# SDRAMModule.net
KiCad netlist of a schematic drawn in Altium Designer
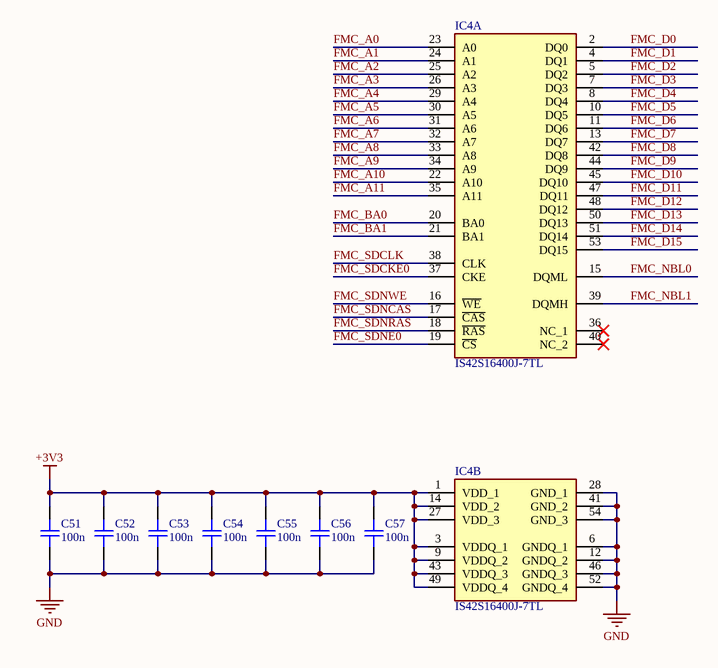
[diagram p0: SDRAMModule.SchDoc]

(export (version "E")
  (design (tool "Eeschema 10.0.6"))
  (components
    (comp (ref "C51")
      (value "100n")
      (footprint "CAP_0402")
      (description "Capacitor SMD 0402")
      (libsource (lib "Schematic-Lib-PhilsLab") (part "CAP_0402"))
    )
    (comp (ref "C52")
      (value "100n")
      (footprint "CAP_0402")
      (description "Capacitor SMD 0402")
      (libsource (lib "Schematic-Lib-PhilsLab") (part "CAP_0402"))
    )
    (comp (ref "C53")
      (value "100n")
      (footprint "CAP_0402")
      (description "Capacitor SMD 0402")
      (libsource (lib "Schematic-Lib-PhilsLab") (part "CAP_0402"))
    )
    (comp (ref "C54")
      (value "100n")
      (footprint "CAP_0402")
      (description "Capacitor SMD 0402")
      (libsource (lib "Schematic-Lib-PhilsLab") (part "CAP_0402"))
    )
    (comp (ref "C55")
      (value "100n")
      (footprint "CAP_0402")
      (description "Capacitor SMD 0402")
      (libsource (lib "Schematic-Lib-PhilsLab") (part "CAP_0402"))
    )
    (comp (ref "C56")
      (value "100n")
      (footprint "CAP_0402")
      (description "Capacitor SMD 0402")
      (libsource (lib "Schematic-Lib-PhilsLab") (part "CAP_0402"))
    )
    (comp (ref "C57")
      (value "100n")
      (footprint "CAP_0402")
      (description "Capacitor SMD 0402")
      (libsource (lib "Schematic-Lib-PhilsLab") (part "CAP_0402"))
    )
    (comp (ref "IC4")
      (value "IS42S16400J-7TL")
      (footprint "Footprint-Lib-PhilsLab:SOP80P1176X120-54N")
      (description "Integrated Circuit")
      (fields (field (name "MOUSER PART NUMBER") "870-IS42S16400J-7TL"))
      (libsource (lib "Schematic-Lib-PhilsLab") (part "IS42S16400J-7TL"))
    )
  )
  (nets
    (net (code "1") (name "+3V3") (class "Default")
      (node (ref "C51") (pin "2") (pinfunction "2_2") (pintype "passive"))
      (node (ref "C52") (pin "2") (pinfunction "2_2") (pintype "passive"))
      (node (ref "C53") (pin "2") (pinfunction "2_2") (pintype "passive"))
      (node (ref "C54") (pin "2") (pinfunction "2_2") (pintype "passive"))
      (node (ref "C55") (pin "2") (pinfunction "2_2") (pintype "passive"))
      (node (ref "C56") (pin "2") (pinfunction "2_2") (pintype "passive"))
      (node (ref "C57") (pin "2") (pinfunction "2_2") (pintype "passive"))
      (node (ref "IC4") (pin "1") (pinfunction "VDD_1_1") (pintype "passive"))
      (node (ref "IC4") (pin "14") (pinfunction "VDD_2_14") (pintype "passive"))
      (node (ref "IC4") (pin "27") (pinfunction "VDD_3_27") (pintype "passive"))
      (node (ref "IC4") (pin "3") (pinfunction "VDDQ_1_3") (pintype "passive"))
      (node (ref "IC4") (pin "43") (pinfunction "VDDQ_3_43") (pintype "passive"))
      (node (ref "IC4") (pin "49") (pinfunction "VDDQ_4_49") (pintype "passive"))
      (node (ref "IC4") (pin "9") (pinfunction "VDDQ_2_9") (pintype "passive"))
    )
    (net (code "2") (name "/FMC_A0") (class "Default")
      (node (ref "IC4") (pin "23") (pinfunction "A0_23") (pintype "passive"))
    )
    (net (code "3") (name "/FMC_A1") (class "Default")
      (node (ref "IC4") (pin "24") (pinfunction "A1_24") (pintype "passive"))
    )
    (net (code "4") (name "/FMC_A2") (class "Default")
      (node (ref "IC4") (pin "25") (pinfunction "A2_25") (pintype "passive"))
    )
    (net (code "5") (name "/FMC_A3") (class "Default")
      (node (ref "IC4") (pin "26") (pinfunction "A3_26") (pintype "passive"))
    )
    (net (code "6") (name "/FMC_A4") (class "Default")
      (node (ref "IC4") (pin "29") (pinfunction "A4_29") (pintype "passive"))
    )
    (net (code "7") (name "/FMC_A5") (class "Default")
      (node (ref "IC4") (pin "30") (pinfunction "A5_30") (pintype "passive"))
    )
    (net (code "8") (name "/FMC_A6") (class "Default")
      (node (ref "IC4") (pin "31") (pinfunction "A6_31") (pintype "passive"))
    )
    (net (code "9") (name "/FMC_A7") (class "Default")
      (node (ref "IC4") (pin "32") (pinfunction "A7_32") (pintype "passive"))
    )
    (net (code "10") (name "/FMC_A8") (class "Default")
      (node (ref "IC4") (pin "33") (pinfunction "A8_33") (pintype "passive"))
    )
    (net (code "11") (name "/FMC_A9") (class "Default")
      (node (ref "IC4") (pin "34") (pinfunction "A9_34") (pintype "passive"))
    )
    (net (code "12") (name "/FMC_A10") (class "Default")
      (node (ref "IC4") (pin "22") (pinfunction "A10_22") (pintype "passive"))
    )
    (net (code "13") (name "/FMC_A11") (class "Default")
      (node (ref "IC4") (pin "35") (pinfunction "A11_35") (pintype "passive"))
    )
    (net (code "14") (name "/FMC_BA0") (class "Default")
      (node (ref "IC4") (pin "20") (pinfunction "BA0_20") (pintype "passive"))
    )
    (net (code "15") (name "/FMC_BA1") (class "Default")
      (node (ref "IC4") (pin "21") (pinfunction "BA1_21") (pintype "passive"))
    )
    (net (code "16") (name "/FMC_D0") (class "Default")
      (node (ref "IC4") (pin "2") (pinfunction "DQ0_2") (pintype "passive"))
    )
    (net (code "17") (name "/FMC_D1") (class "Default")
      (node (ref "IC4") (pin "4") (pinfunction "DQ1_4") (pintype "passive"))
    )
    (net (code "18") (name "/FMC_D2") (class "Default")
      (node (ref "IC4") (pin "5") (pinfunction "DQ2_5") (pintype "passive"))
    )
    (net (code "19") (name "/FMC_D3") (class "Default")
      (node (ref "IC4") (pin "7") (pinfunction "DQ3_7") (pintype "passive"))
    )
    (net (code "20") (name "/FMC_D4") (class "Default")
      (node (ref "IC4") (pin "8") (pinfunction "DQ4_8") (pintype "passive"))
    )
    (net (code "21") (name "/FMC_D5") (class "Default")
      (node (ref "IC4") (pin "10") (pinfunction "DQ5_10") (pintype "passive"))
    )
    (net (code "22") (name "/FMC_D6") (class "Default")
      (node (ref "IC4") (pin "11") (pinfunction "DQ6_11") (pintype "passive"))
    )
    (net (code "23") (name "/FMC_D7") (class "Default")
      (node (ref "IC4") (pin "13") (pinfunction "DQ7_13") (pintype "passive"))
    )
    (net (code "24") (name "/FMC_D8") (class "Default")
      (node (ref "IC4") (pin "42") (pinfunction "DQ8_42") (pintype "passive"))
    )
    (net (code "25") (name "/FMC_D9") (class "Default")
      (node (ref "IC4") (pin "44") (pinfunction "DQ9_44") (pintype "passive"))
    )
    (net (code "26") (name "/FMC_D10") (class "Default")
      (node (ref "IC4") (pin "45") (pinfunction "DQ10_45") (pintype "passive"))
    )
    (net (code "27") (name "/FMC_D11") (class "Default")
      (node (ref "IC4") (pin "47") (pinfunction "DQ11_47") (pintype "passive"))
    )
    (net (code "28") (name "/FMC_D12") (class "Default")
      (node (ref "IC4") (pin "48") (pinfunction "DQ12_48") (pintype "passive"))
    )
    (net (code "29") (name "/FMC_D13") (class "Default")
      (node (ref "IC4") (pin "50") (pinfunction "DQ13_50") (pintype "passive"))
    )
    (net (code "30") (name "/FMC_D14") (class "Default")
      (node (ref "IC4") (pin "51") (pinfunction "DQ14_51") (pintype "passive"))
    )
    (net (code "31") (name "/FMC_D15") (class "Default")
      (node (ref "IC4") (pin "53") (pinfunction "DQ15_53") (pintype "passive"))
    )
    (net (code "32") (name "/FMC_NBL0") (class "Default")
      (node (ref "IC4") (pin "15") (pinfunction "DQML_15") (pintype "passive"))
    )
    (net (code "33") (name "/FMC_NBL1") (class "Default")
      (node (ref "IC4") (pin "39") (pinfunction "DQMH_39") (pintype "passive"))
    )
    (net (code "34") (name "/FMC_SDCKE0") (class "Default")
      (node (ref "IC4") (pin "37") (pinfunction "CKE_37") (pintype "passive"))
    )
    (net (code "35") (name "/FMC_SDCLK") (class "Default")
      (node (ref "IC4") (pin "38") (pinfunction "CLK_38") (pintype "passive"))
    )
    (net (code "36") (name "/FMC_SDNCAS") (class "Default")
      (node (ref "IC4") (pin "17") (pinfunction "~{CAS}_17") (pintype "passive"))
    )
    (net (code "37") (name "/FMC_SDNE0") (class "Default")
      (node (ref "IC4") (pin "19") (pinfunction "~{CS}_19") (pintype "passive"))
    )
    (net (code "38") (name "/FMC_SDNRAS") (class "Default")
      (node (ref "IC4") (pin "18") (pinfunction "~{RAS}_18") (pintype "passive"))
    )
    (net (code "39") (name "/FMC_SDNWE") (class "Default")
      (node (ref "IC4") (pin "16") (pinfunction "~{WE}_16") (pintype "passive"))
    )
    (net (code "40") (name "GND") (class "Default")
      (node (ref "C51") (pin "1") (pinfunction "1_1") (pintype "passive"))
      (node (ref "C52") (pin "1") (pinfunction "1_1") (pintype "passive"))
      (node (ref "C53") (pin "1") (pinfunction "1_1") (pintype "passive"))
      (node (ref "C54") (pin "1") (pinfunction "1_1") (pintype "passive"))
      (node (ref "C55") (pin "1") (pinfunction "1_1") (pintype "passive"))
      (node (ref "C56") (pin "1") (pinfunction "1_1") (pintype "passive"))
      (node (ref "C57") (pin "1") (pinfunction "1_1") (pintype "passive"))
      (node (ref "IC4") (pin "12") (pinfunction "GNDQ_2_12") (pintype "passive"))
      (node (ref "IC4") (pin "28") (pinfunction "GND_1_28") (pintype "passive"))
      (node (ref "IC4") (pin "41") (pinfunction "GND_2_41") (pintype "passive"))
      (node (ref "IC4") (pin "46") (pinfunction "GNDQ_3_46") (pintype "passive"))
      (node (ref "IC4") (pin "52") (pinfunction "GNDQ_4_52") (pintype "passive"))
      (node (ref "IC4") (pin "54") (pinfunction "GND_3_54") (pintype "passive"))
      (node (ref "IC4") (pin "6") (pinfunction "GNDQ_1_6") (pintype "passive"))
    )
    (net (code "41") (name "unconnected-(IC4A-NC_1-Pad36)") (class "Default")
      (node (ref "IC4") (pin "36") (pinfunction "NC_1_36") (pintype "passive+no_connect"))
    )
    (net (code "42") (name "unconnected-(IC4A-NC_2-Pad40)") (class "Default")
      (node (ref "IC4") (pin "40") (pinfunction "NC_2_40") (pintype "passive+no_connect"))
    )
  )
)
